# microcontroller_module.net
KiCad netlist of a schematic drawn in Altium Designer
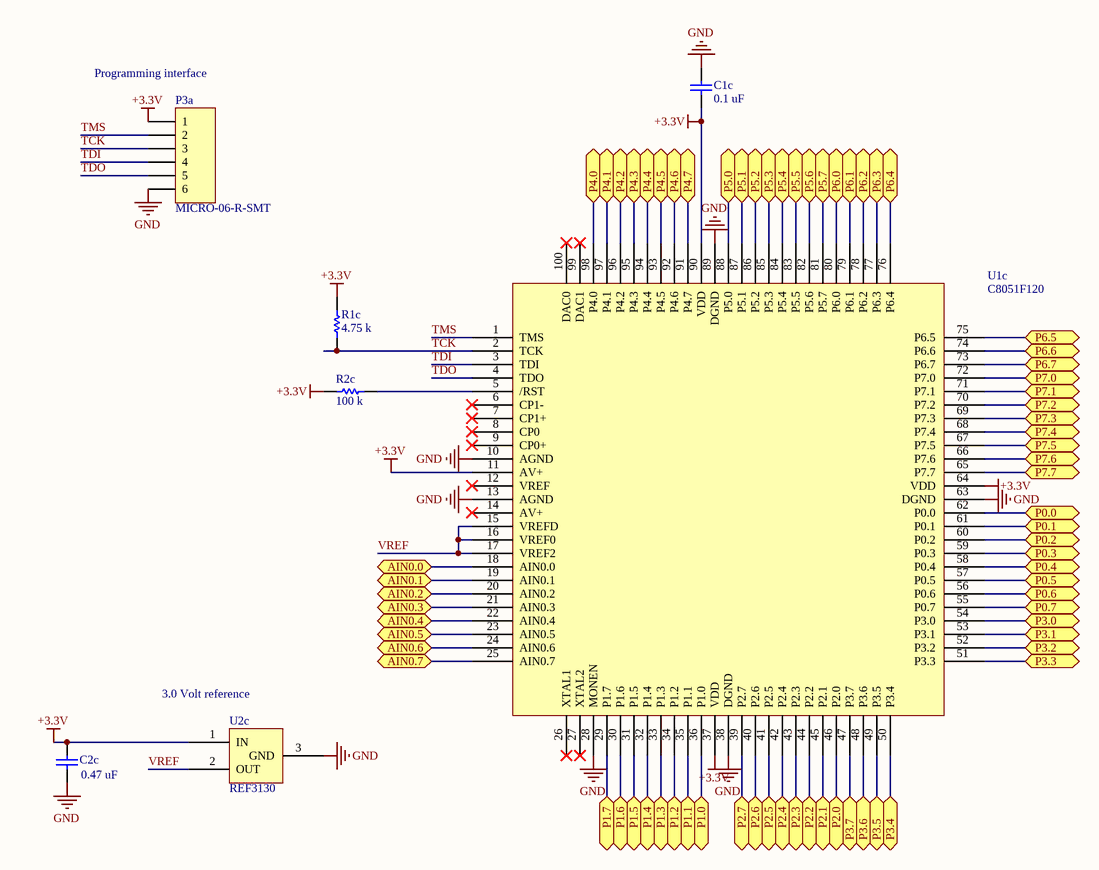
[diagram p0: microcontroller module.SchDoc]

(export (version "E")
  (design (tool "Eeschema 10.0.6"))
  (components
    (comp (ref "C1c") (value "0.1 uF") (footprint "0603") (libsource (lib "allspace_schem") (part "Cap")))
    (comp (ref "C2c")
      (value "0.47 uF")
      (footprint "0603")
      (fields (field (name "PUBLISHER") "Altium Limited"))
      (libsource (lib "Miscellaneous Devices") (part "Cap"))
    )
    (comp (ref "P3a")
      (value "MICRO-06-R-SMT")
      (footprint "MICRO-06-R-SMT")
      (description "Micro Connector")
      (libsource (lib "allspace_schem") (part "MICRO-06"))
    )
    (comp (ref "R1c") (value "4.75 k") (footprint "0603") (libsource (lib "allspace_schem") (part "Res")))
    (comp (ref "R2c") (value "100 k") (footprint "0603") (libsource (lib "allspace_schem") (part "Res")))
    (comp (ref "U1c")
      (value "C8051F120")
      (footprint "TQFP-100")
      (description "Microcontroller")
      (libsource (lib "allspace_schem") (part "C8051F120"))
    )
    (comp (ref "U2c")
      (value "REF3130")
      (footprint "SOT23-3")
      (description "296-17098-1-ND")
      (libsource (lib "allspace_schem") (part "REF3130"))
    )
  )
  (nets
    (net (code "1") (name "+3.3V") (class "Default")
      (node (ref "C1c") (pin "2") (pinfunction "2_2") (pintype "passive"))
      (node (ref "C2c") (pin "1") (pinfunction "1_1") (pintype "passive"))
      (node (ref "P3a") (pin "1") (pinfunction "1_1") (pintype "passive"))
      (node (ref "R1c") (pin "2") (pinfunction "2_2") (pintype "passive"))
      (node (ref "R2c") (pin "2") (pinfunction "2_2") (pintype "passive"))
      (node (ref "U1c") (pin "11") (pinfunction "AV+_11") (pintype "passive"))
      (node (ref "U1c") (pin "37") (pinfunction "VDD_37") (pintype "passive"))
      (node (ref "U1c") (pin "64") (pinfunction "VDD_64") (pintype "passive"))
      (node (ref "U1c") (pin "90") (pinfunction "VDD_90") (pintype "passive"))
      (node (ref "U2c") (pin "1") (pinfunction "IN_1") (pintype "passive"))
    )
    (net (code "2") (name "/AIN0.0") (class "Default")
      (node (ref "U1c") (pin "18") (pinfunction "AIN0.0_18") (pintype "passive"))
    )
    (net (code "3") (name "/AIN0.1") (class "Default")
      (node (ref "U1c") (pin "19") (pinfunction "AIN0.1_19") (pintype "passive"))
    )
    (net (code "4") (name "/AIN0.2") (class "Default")
      (node (ref "U1c") (pin "20") (pinfunction "AIN0.2_20") (pintype "passive"))
    )
    (net (code "5") (name "/AIN0.3") (class "Default")
      (node (ref "U1c") (pin "21") (pinfunction "AIN0.3_21") (pintype "passive"))
    )
    (net (code "6") (name "/AIN0.4") (class "Default")
      (node (ref "U1c") (pin "22") (pinfunction "AIN0.4_22") (pintype "passive"))
    )
    (net (code "7") (name "/AIN0.5") (class "Default")
      (node (ref "U1c") (pin "23") (pinfunction "AIN0.5_23") (pintype "passive"))
    )
    (net (code "8") (name "/AIN0.6") (class "Default")
      (node (ref "U1c") (pin "24") (pinfunction "AIN0.6_24") (pintype "passive"))
    )
    (net (code "9") (name "/AIN0.7") (class "Default")
      (node (ref "U1c") (pin "25") (pinfunction "AIN0.7_25") (pintype "passive"))
    )
    (net (code "10") (name "/P0.0") (class "Default")
      (node (ref "U1c") (pin "62") (pinfunction "P0.0_62") (pintype "passive"))
    )
    (net (code "11") (name "/P0.1") (class "Default")
      (node (ref "U1c") (pin "61") (pinfunction "P0.1_61") (pintype "passive"))
    )
    (net (code "12") (name "/P0.2") (class "Default")
      (node (ref "U1c") (pin "60") (pinfunction "P0.2_60") (pintype "passive"))
    )
    (net (code "13") (name "/P0.3") (class "Default")
      (node (ref "U1c") (pin "59") (pinfunction "P0.3_59") (pintype "passive"))
    )
    (net (code "14") (name "/P0.4") (class "Default")
      (node (ref "U1c") (pin "58") (pinfunction "P0.4_58") (pintype "passive"))
    )
    (net (code "15") (name "/P0.5") (class "Default")
      (node (ref "U1c") (pin "57") (pinfunction "P0.5_57") (pintype "passive"))
    )
    (net (code "16") (name "/P0.6") (class "Default")
      (node (ref "U1c") (pin "56") (pinfunction "P0.6_56") (pintype "passive"))
    )
    (net (code "17") (name "/P0.7") (class "Default")
      (node (ref "U1c") (pin "55") (pinfunction "P0.7_55") (pintype "passive"))
    )
    (net (code "18") (name "/P1.0") (class "Default")
      (node (ref "U1c") (pin "36") (pinfunction "P1.0_36") (pintype "passive"))
    )
    (net (code "19") (name "/P1.1") (class "Default")
      (node (ref "U1c") (pin "35") (pinfunction "P1.1_35") (pintype "passive"))
    )
    (net (code "20") (name "/P1.2") (class "Default")
      (node (ref "U1c") (pin "34") (pinfunction "P1.2_34") (pintype "passive"))
    )
    (net (code "21") (name "/P1.3") (class "Default")
      (node (ref "U1c") (pin "33") (pinfunction "P1.3_33") (pintype "passive"))
    )
    (net (code "22") (name "/P1.4") (class "Default")
      (node (ref "U1c") (pin "32") (pinfunction "P1.4_32") (pintype "passive"))
    )
    (net (code "23") (name "/P1.5") (class "Default")
      (node (ref "U1c") (pin "31") (pinfunction "P1.5_31") (pintype "passive"))
    )
    (net (code "24") (name "/P1.6") (class "Default")
      (node (ref "U1c") (pin "30") (pinfunction "P1.6_30") (pintype "passive"))
    )
    (net (code "25") (name "/P1.7") (class "Default")
      (node (ref "U1c") (pin "29") (pinfunction "P1.7_29") (pintype "passive"))
    )
    (net (code "26") (name "/P2.0") (class "Default")
      (node (ref "U1c") (pin "46") (pinfunction "P2.0_46") (pintype "passive"))
    )
    (net (code "27") (name "/P2.1") (class "Default")
      (node (ref "U1c") (pin "45") (pinfunction "P2.1_45") (pintype "passive"))
    )
    (net (code "28") (name "/P2.2") (class "Default")
      (node (ref "U1c") (pin "44") (pinfunction "P2.2_44") (pintype "passive"))
    )
    (net (code "29") (name "/P2.3") (class "Default")
      (node (ref "U1c") (pin "43") (pinfunction "P2.3_43") (pintype "passive"))
    )
    (net (code "30") (name "/P2.4") (class "Default")
      (node (ref "U1c") (pin "42") (pinfunction "P2.4_42") (pintype "passive"))
    )
    (net (code "31") (name "/P2.5") (class "Default")
      (node (ref "U1c") (pin "41") (pinfunction "P2.5_41") (pintype "passive"))
    )
    (net (code "32") (name "/P2.6") (class "Default")
      (node (ref "U1c") (pin "40") (pinfunction "P2.6_40") (pintype "passive"))
    )
    (net (code "33") (name "/P2.7") (class "Default")
      (node (ref "U1c") (pin "39") (pinfunction "P2.7_39") (pintype "passive"))
    )
    (net (code "34") (name "/P3.0") (class "Default")
      (node (ref "U1c") (pin "54") (pinfunction "P3.0_54") (pintype "passive"))
    )
    (net (code "35") (name "/P3.1") (class "Default")
      (node (ref "U1c") (pin "53") (pinfunction "P3.1_53") (pintype "passive"))
    )
    (net (code "36") (name "/P3.2") (class "Default")
      (node (ref "U1c") (pin "52") (pinfunction "P3.2_52") (pintype "passive"))
    )
    (net (code "37") (name "/P3.3") (class "Default")
      (node (ref "U1c") (pin "51") (pinfunction "P3.3_51") (pintype "passive"))
    )
    (net (code "38") (name "/P3.4") (class "Default")
      (node (ref "U1c") (pin "50") (pinfunction "P3.4_50") (pintype "passive"))
    )
    (net (code "39") (name "/P3.5") (class "Default")
      (node (ref "U1c") (pin "49") (pinfunction "P3.5_49") (pintype "passive"))
    )
    (net (code "40") (name "/P3.6") (class "Default")
      (node (ref "U1c") (pin "48") (pinfunction "P3.6_48") (pintype "passive"))
    )
    (net (code "41") (name "/P3.7") (class "Default")
      (node (ref "U1c") (pin "47") (pinfunction "P3.7_47") (pintype "passive"))
    )
    (net (code "42") (name "/P4.0") (class "Default")
      (node (ref "U1c") (pin "98") (pinfunction "P4.0_98") (pintype "passive"))
    )
    (net (code "43") (name "/P4.1") (class "Default")
      (node (ref "U1c") (pin "97") (pinfunction "P4.1_97") (pintype "passive"))
    )
    (net (code "44") (name "/P4.2") (class "Default")
      (node (ref "U1c") (pin "96") (pinfunction "P4.2_96") (pintype "passive"))
    )
    (net (code "45") (name "/P4.3") (class "Default")
      (node (ref "U1c") (pin "95") (pinfunction "P4.3_95") (pintype "passive"))
    )
    (net (code "46") (name "/P4.4") (class "Default")
      (node (ref "U1c") (pin "94") (pinfunction "P4.4_94") (pintype "passive"))
    )
    (net (code "47") (name "/P4.5") (class "Default")
      (node (ref "U1c") (pin "93") (pinfunction "P4.5_93") (pintype "passive"))
    )
    (net (code "48") (name "/P4.6") (class "Default")
      (node (ref "U1c") (pin "92") (pinfunction "P4.6_92") (pintype "passive"))
    )
    (net (code "49") (name "/P4.7") (class "Default")
      (node (ref "U1c") (pin "91") (pinfunction "P4.7_91") (pintype "passive"))
    )
    (net (code "50") (name "/P5.0") (class "Default")
      (node (ref "U1c") (pin "88") (pinfunction "P5.0_88") (pintype "passive"))
    )
    (net (code "51") (name "/P5.1") (class "Default")
      (node (ref "U1c") (pin "87") (pinfunction "P5.1_87") (pintype "passive"))
    )
    (net (code "52") (name "/P5.2") (class "Default")
      (node (ref "U1c") (pin "86") (pinfunction "P5.2_86") (pintype "passive"))
    )
    (net (code "53") (name "/P5.3") (class "Default")
      (node (ref "U1c") (pin "85") (pinfunction "P5.3_85") (pintype "passive"))
    )
    (net (code "54") (name "/P5.4") (class "Default")
      (node (ref "U1c") (pin "84") (pinfunction "P5.4_84") (pintype "passive"))
    )
    (net (code "55") (name "/P5.5") (class "Default")
      (node (ref "U1c") (pin "83") (pinfunction "P5.5_83") (pintype "passive"))
    )
    (net (code "56") (name "/P5.6") (class "Default")
      (node (ref "U1c") (pin "82") (pinfunction "P5.6_82") (pintype "passive"))
    )
    (net (code "57") (name "/P5.7") (class "Default")
      (node (ref "U1c") (pin "81") (pinfunction "P5.7_81") (pintype "passive"))
    )
    (net (code "58") (name "/P6.0") (class "Default")
      (node (ref "U1c") (pin "80") (pinfunction "P6.0_80") (pintype "passive"))
    )
    (net (code "59") (name "/P6.1") (class "Default")
      (node (ref "U1c") (pin "79") (pinfunction "P6.1_79") (pintype "passive"))
    )
    (net (code "60") (name "/P6.2") (class "Default")
      (node (ref "U1c") (pin "78") (pinfunction "P6.2_78") (pintype "passive"))
    )
    (net (code "61") (name "/P6.3") (class "Default")
      (node (ref "U1c") (pin "77") (pinfunction "P6.3_77") (pintype "passive"))
    )
    (net (code "62") (name "/P6.4") (class "Default")
      (node (ref "U1c") (pin "76") (pinfunction "P6.4_76") (pintype "passive"))
    )
    (net (code "63") (name "/P6.5") (class "Default")
      (node (ref "U1c") (pin "75") (pinfunction "P6.5_75") (pintype "passive"))
    )
    (net (code "64") (name "/P6.6") (class "Default")
      (node (ref "U1c") (pin "74") (pinfunction "P6.6_74") (pintype "passive"))
    )
    (net (code "65") (name "/P6.7") (class "Default")
      (node (ref "U1c") (pin "73") (pinfunction "P6.7_73") (pintype "passive"))
    )
    (net (code "66") (name "/P7.0") (class "Default")
      (node (ref "U1c") (pin "72") (pinfunction "P7.0_72") (pintype "passive"))
    )
    (net (code "67") (name "/P7.1") (class "Default")
      (node (ref "U1c") (pin "71") (pinfunction "P7.1_71") (pintype "passive"))
    )
    (net (code "68") (name "/P7.2") (class "Default")
      (node (ref "U1c") (pin "70") (pinfunction "P7.2_70") (pintype "passive"))
    )
    (net (code "69") (name "/P7.3") (class "Default")
      (node (ref "U1c") (pin "69") (pinfunction "P7.3_69") (pintype "passive"))
    )
    (net (code "70") (name "/P7.4") (class "Default")
      (node (ref "U1c") (pin "68") (pinfunction "P7.4_68") (pintype "passive"))
    )
    (net (code "71") (name "/P7.5") (class "Default")
      (node (ref "U1c") (pin "67") (pinfunction "P7.5_67") (pintype "passive"))
    )
    (net (code "72") (name "/P7.6") (class "Default")
      (node (ref "U1c") (pin "66") (pinfunction "P7.6_66") (pintype "passive"))
    )
    (net (code "73") (name "/P7.7") (class "Default")
      (node (ref "U1c") (pin "65") (pinfunction "P7.7_65") (pintype "passive"))
    )
    (net (code "74") (name "/TCK") (class "Default")
      (node (ref "P3a") (pin "3") (pinfunction "3_3") (pintype "passive"))
      (node (ref "R1c") (pin "1") (pinfunction "1_1") (pintype "passive"))
      (node (ref "U1c") (pin "2") (pinfunction "TCK_2") (pintype "passive"))
    )
    (net (code "75") (name "/TDI") (class "Default")
      (node (ref "P3a") (pin "4") (pinfunction "4_4") (pintype "passive"))
      (node (ref "U1c") (pin "3") (pinfunction "TDI_3") (pintype "passive"))
    )
    (net (code "76") (name "/TDO") (class "Default")
      (node (ref "P3a") (pin "5") (pinfunction "5_5") (pintype "passive"))
      (node (ref "U1c") (pin "4") (pinfunction "TDO_4") (pintype "passive"))
    )
    (net (code "77") (name "/TMS") (class "Default")
      (node (ref "P3a") (pin "2") (pinfunction "2_2") (pintype "passive"))
      (node (ref "U1c") (pin "1") (pinfunction "TMS_1") (pintype "passive"))
    )
    (net (code "78") (name "/VREF") (class "Default")
      (node (ref "U1c") (pin "15") (pinfunction "VREFD_15") (pintype "passive"))
      (node (ref "U1c") (pin "16") (pinfunction "VREF0_16") (pintype "passive"))
      (node (ref "U1c") (pin "17") (pinfunction "VREF2_17") (pintype "passive"))
      (node (ref "U2c") (pin "2") (pinfunction "OUT_2") (pintype "passive"))
    )
    (net (code "79") (name "GND") (class "Default")
      (node (ref "C1c") (pin "1") (pinfunction "1_1") (pintype "passive"))
      (node (ref "C2c") (pin "2") (pinfunction "2_2") (pintype "passive"))
      (node (ref "P3a") (pin "6") (pinfunction "6_6") (pintype "passive"))
      (node (ref "U1c") (pin "10") (pinfunction "AGND_10") (pintype "passive"))
      (node (ref "U1c") (pin "13") (pinfunction "AGND_13") (pintype "passive"))
      (node (ref "U1c") (pin "28") (pinfunction "MONEN_28") (pintype "passive"))
      (node (ref "U1c") (pin "38") (pinfunction "DGND_38") (pintype "passive"))
      (node (ref "U1c") (pin "63") (pinfunction "DGND_63") (pintype "passive"))
      (node (ref "U1c") (pin "89") (pinfunction "DGND_89") (pintype "passive"))
      (node (ref "U2c") (pin "3") (pinfunction "GND_3") (pintype "passive"))
    )
    (net (code "80") (name "Net-(U1c-{slash}RST)") (class "Default")
      (node (ref "R2c") (pin "1") (pinfunction "1_1") (pintype "passive"))
      (node (ref "U1c") (pin "5") (pinfunction "/RST_5") (pintype "passive"))
    )
    (net (code "81") (name "unconnected-(U1c-AV+-Pad14)") (class "Default")
      (node (ref "U1c") (pin "14") (pinfunction "AV+_14") (pintype "passive+no_connect"))
    )
    (net (code "82") (name "unconnected-(U1c-CP0+-Pad9)") (class "Default")
      (node (ref "U1c") (pin "9") (pinfunction "CP0+_9") (pintype "passive+no_connect"))
    )
    (net (code "83") (name "unconnected-(U1c-CP0-Pad8)") (class "Default")
      (node (ref "U1c") (pin "8") (pinfunction "CP0_8") (pintype "passive+no_connect"))
    )
    (net (code "84") (name "unconnected-(U1c-CP1+-Pad7)") (class "Default")
      (node (ref "U1c") (pin "7") (pinfunction "CP1+_7") (pintype "passive+no_connect"))
    )
    (net (code "85") (name "unconnected-(U1c-CP1--Pad6)") (class "Default")
      (node (ref "U1c") (pin "6") (pinfunction "CP1-_6") (pintype "passive+no_connect"))
    )
    (net (code "86") (name "unconnected-(U1c-DAC0-Pad100)") (class "Default")
      (node (ref "U1c") (pin "100") (pinfunction "DAC0_100") (pintype "passive+no_connect"))
    )
    (net (code "87") (name "unconnected-(U1c-DAC1-Pad99)") (class "Default")
      (node (ref "U1c") (pin "99") (pinfunction "DAC1_99") (pintype "passive+no_connect"))
    )
    (net (code "88") (name "unconnected-(U1c-VREF-Pad12)") (class "Default")
      (node (ref "U1c") (pin "12") (pinfunction "VREF_12") (pintype "passive+no_connect"))
    )
    (net (code "89") (name "unconnected-(U1c-XTAL1-Pad26)") (class "Default")
      (node (ref "U1c") (pin "26") (pinfunction "XTAL1_26") (pintype "passive+no_connect"))
    )
    (net (code "90") (name "unconnected-(U1c-XTAL2-Pad27)") (class "Default")
      (node (ref "U1c") (pin "27") (pinfunction "XTAL2_27") (pintype "passive+no_connect"))
    )
  )
)
